# Power_Board.net
KiCad netlist of a schematic drawn in Altium Designer
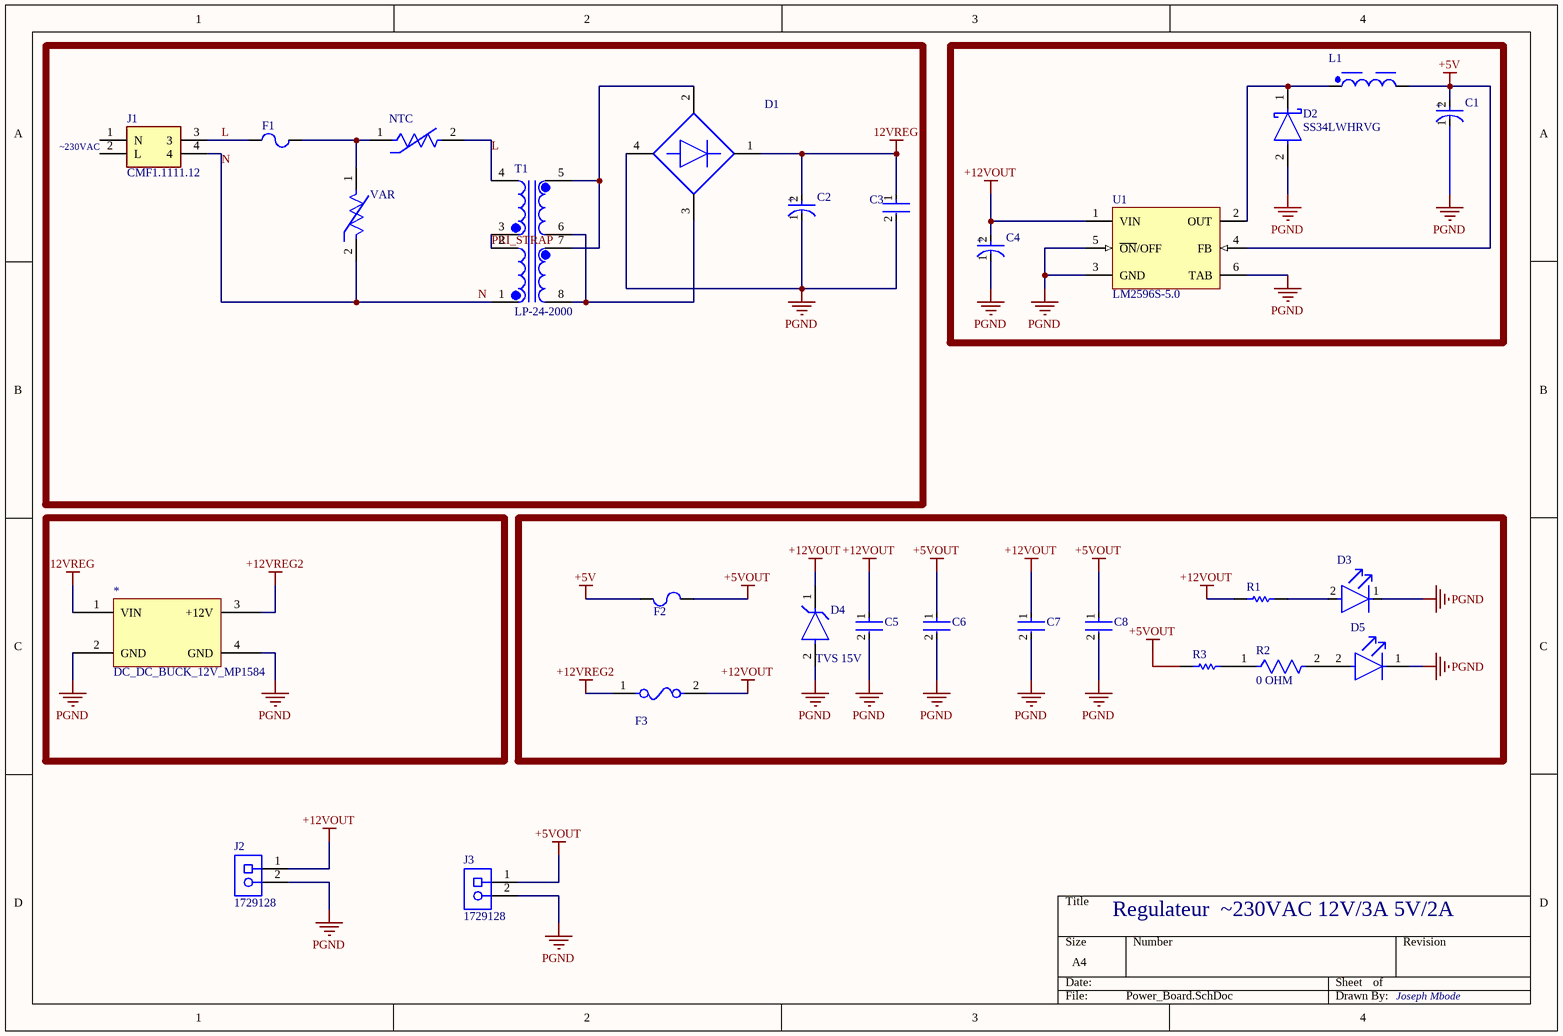
[diagram p0: Power_Board.SchDoc]

(export (version "E")
  (design (tool "Eeschema 10.0.6"))
  (components
    (comp (ref "*")
      (value "DC_DC_BUCK_12V_MP1584")
      (footprint "DC_DC_BUCK_12V_MP1584")
      (libsource (lib "Power_Modules") (part "DC_DC_BUCK_12V_MP1584"))
    )
    (comp (ref "C1")
      (value "EEVTG1H221Q")
      (footprint "FP-TGH13-MFG")
      (description "CAP ALUM 220UF 20% 50V SMD")
      (fields
        (field (name "MANUFACTURER") "Panasonic Electronic Components")
        (field (name "TOLERANCE") "20%")
      )
      (libsource (lib "Altium Content Vault") (part "cf48714ba7e38822c1575c7ec0b6d1f"))
    )
    (comp (ref "C2")
      (value "ECA1VHG472")
      (footprint "FP-RAD-TH-D_18_0_5-L_35_5-MFG")
      (description "Aluminum Electrolytic Capacitors (Radial Lead Type) AEC-Q200 Qualified 4700uF ±20% 35V")
      (fields (field (name "VOLTAGE") "35V") (field (name "TOLERANCE") "20%"))
      (libsource (lib "Altium Content Vault") (part "203bc49f2ac43e59fd269a8c329ed05"))
    )
    (comp (ref "C3")
      (value "RHEL81H155K2A2H03B")
      (footprint "FP-RHE2DB-MFG")
      (description "Ceramic Capacitor Automotive 1.5uF ±10% 50V X8L Radial")
      (fields (field (name "TOLERANCE") "10%"))
      (libsource (lib "Altium Content Vault") (part "02cd4be3c70576c341d710602a673aa"))
    )
    (comp (ref "C4")
      (value "EEUFR1E221")
      (footprint "FP-RAD-TH-D_8_0_5-L_11_5-MFG")
      (description "Aluminum Electrolytic Capacitors (Radial Lead Type) 220uF ±20% 25V")
      (fields (field (name "VOLTAGE") "25V") (field (name "TOLERANCE") "20%"))
      (libsource (lib "Altium Content Vault") (part "a00bbbee19879c290e62620ae7e47b1"))
    )
    (comp (ref "C5")
      (value "AC1206KKX7R0BB104")
      (footprint "FP-AC1206-0_85-MFG")
      (description "CAP CER 0.1UF 100V X7R 1206")
      (fields
        (field (name "OCTOPART") "https://octopart.com/ac1206kkx7r0bb104-yageo-75666120")
        (field (name "TOLERANCE") "0.1")
      )
      (libsource (lib "Altium Content Vault") (part "11868f565c42a9108669ba33697ecf6"))
    )
    (comp (ref "C6")
      (value "AC1206KKX7R0BB104")
      (footprint "FP-AC1206-0_85-MFG")
      (description "CAP CER 0.1UF 100V X7R 1206")
      (fields
        (field (name "OCTOPART") "https://octopart.com/ac1206kkx7r0bb104-yageo-75666120")
        (field (name "TOLERANCE") "0.1")
      )
      (libsource (lib "Altium Content Vault") (part "11868f565c42a9108669ba33697ecf6"))
    )
    (comp (ref "C7")
      (value "AC1206KKX7R0BB104")
      (footprint "FP-AC1206-0_85-MFG")
      (description "CAP CER 0.1UF 100V X7R 1206")
      (fields
        (field (name "OCTOPART") "https://octopart.com/ac1206kkx7r0bb104-yageo-75666120")
        (field (name "TOLERANCE") "0.1")
      )
      (libsource (lib "Altium Content Vault") (part "11868f565c42a9108669ba33697ecf6"))
    )
    (comp (ref "C8")
      (value "AC1206KKX7R0BB104")
      (footprint "FP-AC1206-0_85-MFG")
      (description "CAP CER 0.1UF 100V X7R 1206")
      (fields
        (field (name "OCTOPART") "https://octopart.com/ac1206kkx7r0bb104-yageo-75666120")
        (field (name "TOLERANCE") "0.1")
      )
      (libsource (lib "Altium Content Vault") (part "11868f565c42a9108669ba33697ecf6"))
    )
    (comp (ref "D1")
      (value "GBU4M-E3/51")
      (footprint "FP-GBU4M-E3-51-MFG")
      (description "BRIDGE RECT 1PHASE 1KV 3A GBU")
      (libsource (lib "Altium Content Vault") (part "df980e46bdef61da3a5be2ae2fed6b6"))
    )
    (comp (ref "D2")
      (value "SS34LWHRVG")
      (footprint "FP-SS34LWH-MFG")
      (description "DIODE SCHOTTKY 40V 3A SOD123W")
      (libsource (lib "Altium Content Vault") (part "1d6ec82d83fb6aee721767c19dac4b9"))
    )
    (comp (ref "D3")
      (value "XLUR12D")
      (footprint "FP-XLUR12D-MFG")
      (description "627nm Red LED; 5x8.6mm, Through-Hole Mount with Red Diffused Round Lamp")
      (libsource (lib "Altium Content Vault") (part "XLUR12D"))
    )
    (comp (ref "D4")
      (value "TVS 15V")
      (footprint "FP-DO-15-MFG")
      (description "P6KE15A 600 Watt SUR40 Transient Voltage Suppressor, 15 V, Unidirectional")
      (libsource (lib "Altium Content Vault") (part "f813f71cba58e380607f5dd3caf9714"))
    )
    (comp (ref "D5")
      (value "SSL-LX5093YD")
      (footprint "FP-SSL-LX5093YD-MFG")
      (description "LED YELLOW DIFFUSED T-1 3/4 T/H")
      (libsource (lib "Altium Content Vault") (part "8706943c75ba83719d021d2fdc84c58"))
    )
    (comp (ref "F1")
      (value "021502.5MXP")
      (footprint "LFUS-0215-20X5_L")
      (description "Time-Lag Type Cartridge Fuse, 2.5 A, 0.00386 Ohm, 250 V, -55 to 125 degC, 2-Pin SMD, RoHS, Bulk")
      (fields (field (name "MANUFACTURER") "Littelfuse"))
      (libsource (lib "Altium Content Vault") (part "FUSE-2"))
    )
    (comp (ref "F2")
      (value "1812L150ZR")
      (footprint "LFUS-FUSE1812-71_V")
      (description "Resettable PTC, 1812, 1.5 A Ihold, 3.0 A Itrip")
      (libsource (lib "Altium Content Vault") (part "LFUS-FUSE-2"))
    )
    (comp (ref "F3")
      (value "0452004.MRL")
      (footprint "FP-0452-MFG")
      (description "FUSE BRD MNT 4A 125VAC/VDC 2SMD")
      (fields
        (field (name "MANUFACTURER") "Littelfuse Inc")
        (field (name "OCTOPART") "https://octopart.com/0452004.mrl-littelfuse-566421")
      )
      (libsource (lib "Altium Content Vault") (part "5bcf9b9f640e542cf0359d10258e979"))
    )
    (comp (ref "J1")
      (value "CMF1.1111.12")
      (footprint "CMF1111112")
      (fields (field (name "MOUSER PART NUMBER") "693-CMF1.1111.12"))
      (libsource (lib "connecteur CMF1.1111.12") (part "CMF1.1111.12"))
    )
    (comp (ref "J2")
      (value "1729128")
      (footprint "PHOE-1729128-2_V")
      (description "PCB Terminal Block, 13.5 A, 400 V, 2-Pin THD, RoHS, Bulk")
      (fields (field (name "MANUFACTURER") "Phoenix Contact"))
      (libsource (lib "Bornier_tension") (part "CMP-2000-05815-1"))
    )
    (comp (ref "J3")
      (value "1729128")
      (footprint "PHOE-1729128-2_V")
      (description "PCB Terminal Block, 13.5 A, 400 V, 2-Pin THD, RoHS, Bulk")
      (fields (field (name "MANUFACTURER") "Phoenix Contact"))
      (libsource (lib "Bornier_tension") (part "CMP-2000-05815-1"))
    )
    (comp (ref "L1")
      (value "7447471330")
      (footprint "WE-TIS_1111")
      (description "Inductor Power Shielded Wirewound 33uH 20% 1KHz Ferrite 3.6A 61mOhm DCR RDL Tray")
      (fields (field (name "TOLERANCE") "20%"))
      (libsource (lib "Altium Content Vault") (part "Inductor - 2"))
    )
    (comp (ref "NTC")
      (value "NTPAA100LDNB0")
      (footprint "FP-NTPAA-MFG")
      (description "ICL 10 OHM 15% 1.7A 10MM")
      (fields (field (name "TOLERANCE") "15%"))
      (libsource (lib "Altium Content Vault") (part "3b148a6ebabc5fb4d708a66c052d352"))
    )
    (comp (ref "R1")
      (value "3R3 5% 0805(2012)")
      (footprint "RESC0805(2012)_M")
      (description "3R3 0.125W 5% 0805 (2012 Metric)  SMD")
      (fields (field (name "TOLERANCE") "5 %") (field (name "POWER") "0.125 W"))
      (libsource (lib "Altium Content Vault") (part "RES"))
    )
    (comp (ref "R2")
      (value "0 OHM")
      (footprint "FP-CRG0402-IPC_C")
      (description "RES SMD 0 OHM JUMPER 1/16W 0402")
      (fields (field (name "TOLERANCE") "0%"))
      (libsource (lib "Altium Content Vault") (part "1029c3af85768c4190bb7ad29bc67b5"))
    )
    (comp (ref "R3")
      (value "3R3 5% 0805(2012)")
      (footprint "RESC0805(2012)_M")
      (description "3R3 0.125W 5% 0805 (2012 Metric)  SMD")
      (fields (field (name "TOLERANCE") "5 %") (field (name "POWER") "0.125 W"))
      (libsource (lib "Altium Content Vault") (part "RES"))
    )
    (comp (ref "T1")
      (value "LP-24-2000")
      (footprint "XFMR_LP-24-2000")
      (fields (field (name "MF") "Signal Transformer"))
      (libsource (lib "LP-24-2000") (part "LP-24-2000"))
    )
    (comp (ref "U1")
      (value "LM2596S-5.0")
      (footprint "KTT0005B_L")
      (description "SIMPLE SWITCHER® Power Converter 150 KHz 3A Step-Down Voltage Regulator, 5-pin TO-263")
      (fields (field (name "MANUFACTURER") "Texas Instruments"))
      (libsource (lib "Altium Content Vault") (part "PM-REG-LM2575HVS-12"))
    )
    (comp (ref "VAR")
      (value "IsoM5-275-B-L2")
      (footprint "FP-IsoM5-275-B-L2-MFG")
      (description "ISOMOV 5KA 275VRMS BULK IN-LINE")
      (libsource (lib "Altium Content Vault") (part "661cf0b00536afddc445d021c1166cc"))
    )
  )
  (nets
    (net (code "1") (name "+5V") (class "Default")
      (node (ref "C1") (pin "2") (pinfunction "A_2") (pintype "passive"))
      (node (ref "F2") (pin "1") (pinfunction "1_1") (pintype "passive"))
      (node (ref "L1") (pin "2") (pinfunction "2_2") (pintype "passive"))
      (node (ref "U1") (pin "4") (pinfunction "FB_4") (pintype "input"))
    )
    (net (code "2") (name "+5VOUT") (class "Default")
      (node (ref "C6") (pin "1") (pinfunction "1_1") (pintype "passive"))
      (node (ref "C8") (pin "1") (pinfunction "1_1") (pintype "passive"))
      (node (ref "F2") (pin "2") (pinfunction "2_2") (pintype "passive"))
      (node (ref "J3") (pin "1") (pinfunction "1_1") (pintype "passive"))
      (node (ref "R3") (pin "1") (pinfunction "1_1") (pintype "passive"))
    )
    (net (code "3") (name "+12VOUT") (class "Default")
      (node (ref "C4") (pin "2") (pinfunction "A_2") (pintype "passive"))
      (node (ref "C5") (pin "1") (pinfunction "1_1") (pintype "passive"))
      (node (ref "C7") (pin "1") (pinfunction "1_1") (pintype "passive"))
      (node (ref "D4") (pin "1") (pinfunction "C_1") (pintype "passive"))
      (node (ref "F3") (pin "2") (pinfunction "2_2") (pintype "passive"))
      (node (ref "J2") (pin "1") (pinfunction "1_1") (pintype "passive"))
      (node (ref "R1") (pin "1") (pinfunction "1_1") (pintype "passive"))
      (node (ref "U1") (pin "1") (pinfunction "VIN_1") (pintype "power_in"))
    )
    (net (code "4") (name "+12VREG2") (class "Default")
      (node (ref "*") (pin "3") (pinfunction "+12V_3") (pintype "passive"))
      (node (ref "F3") (pin "1") (pinfunction "1_1") (pintype "passive"))
    )
    (net (code "5") (name "/L") (class "Default")
      (node (ref "F1") (pin "1") (pinfunction "1_1") (pintype "passive"))
      (node (ref "J1") (pin "3") (pinfunction "3_3") (pintype "passive"))
      (node (ref "NTC") (pin "2") (pinfunction "2_2") (pintype "passive"))
      (node (ref "T1") (pin "4") (pinfunction "4_4") (pintype "passive"))
    )
    (net (code "6") (name "/N") (class "Default")
      (node (ref "J1") (pin "4") (pinfunction "4_4") (pintype "passive"))
      (node (ref "T1") (pin "1") (pinfunction "1_1") (pintype "passive"))
      (node (ref "VAR") (pin "2") (pinfunction "2_2") (pintype "passive"))
    )
    (net (code "7") (name "/PRI_STRAP") (class "Default")
      (node (ref "T1") (pin "2") (pinfunction "2_2") (pintype "passive"))
      (node (ref "T1") (pin "3") (pinfunction "3_3") (pintype "passive"))
    )
    (net (code "8") (name "12VREG") (class "Default")
      (node (ref "*") (pin "1") (pinfunction "VIN_1") (pintype "passive"))
      (node (ref "C2") (pin "2") (pinfunction "A_2") (pintype "passive"))
      (node (ref "C3") (pin "1") (pinfunction "1_1") (pintype "passive"))
      (node (ref "D1") (pin "1") (pinfunction "+_1") (pintype "passive"))
    )
    (net (code "9") (name "Net-(D1-1_~)") (class "Default")
      (node (ref "D1") (pin "2") (pinfunction "1_~_2") (pintype "passive"))
      (node (ref "T1") (pin "5") (pinfunction "5_5") (pintype "passive"))
      (node (ref "T1") (pin "7") (pinfunction "7_7") (pintype "passive"))
    )
    (net (code "10") (name "Net-(D1-2_~)") (class "Default")
      (node (ref "D1") (pin "3") (pinfunction "2_~_3") (pintype "passive"))
      (node (ref "T1") (pin "6") (pinfunction "6_6") (pintype "passive"))
      (node (ref "T1") (pin "8") (pinfunction "8_8") (pintype "passive"))
    )
    (net (code "11") (name "Net-(D2-C)") (class "Default")
      (node (ref "D2") (pin "1") (pinfunction "C_1") (pintype "passive"))
      (node (ref "L1") (pin "1") (pinfunction "1_1") (pintype "passive"))
      (node (ref "U1") (pin "2") (pinfunction "OUT_2") (pintype "power_in"))
    )
    (net (code "12") (name "Net-(D3-A)") (class "Default")
      (node (ref "D3") (pin "2") (pinfunction "A_2") (pintype "passive"))
      (node (ref "R1") (pin "2") (pinfunction "2_2") (pintype "passive"))
    )
    (net (code "13") (name "Net-(D5-A)") (class "Default")
      (node (ref "D5") (pin "2") (pinfunction "A_2") (pintype "passive"))
      (node (ref "R2") (pin "2") (pinfunction "2_2") (pintype "passive"))
    )
    (net (code "14") (name "Net-(F1-Pad2)") (class "Default")
      (node (ref "F1") (pin "2") (pinfunction "2_2") (pintype "passive"))
      (node (ref "NTC") (pin "1") (pinfunction "1_1") (pintype "passive"))
      (node (ref "VAR") (pin "1") (pinfunction "1_1") (pintype "passive"))
    )
    (net (code "15") (name "Net-(R2-Pad1)") (class "Default")
      (node (ref "R2") (pin "1") (pinfunction "1_1") (pintype "passive"))
      (node (ref "R3") (pin "2") (pinfunction "2_2") (pintype "passive"))
    )
    (net (code "16") (name "PGND") (class "Default")
      (node (ref "*") (pin "2") (pinfunction "GND_2") (pintype "passive"))
      (node (ref "*") (pin "4") (pinfunction "GND_4") (pintype "passive"))
      (node (ref "C1") (pin "1") (pinfunction "C_1") (pintype "passive"))
      (node (ref "C2") (pin "1") (pinfunction "C_1") (pintype "passive"))
      (node (ref "C3") (pin "2") (pinfunction "2_2") (pintype "passive"))
      (node (ref "C4") (pin "1") (pinfunction "C_1") (pintype "passive"))
      (node (ref "C5") (pin "2") (pinfunction "2_2") (pintype "passive"))
      (node (ref "C6") (pin "2") (pinfunction "2_2") (pintype "passive"))
      (node (ref "C7") (pin "2") (pinfunction "2_2") (pintype "passive"))
      (node (ref "C8") (pin "2") (pinfunction "2_2") (pintype "passive"))
      (node (ref "D1") (pin "4") (pinfunction "-_4") (pintype "passive"))
      (node (ref "D2") (pin "2") (pinfunction "A_2") (pintype "passive"))
      (node (ref "D3") (pin "1") (pinfunction "C_1") (pintype "passive"))
      (node (ref "D4") (pin "2") (pinfunction "A_2") (pintype "passive"))
      (node (ref "D5") (pin "1") (pinfunction "C_1") (pintype "passive"))
      (node (ref "J2") (pin "2") (pinfunction "2_2") (pintype "passive"))
      (node (ref "J3") (pin "2") (pinfunction "2_2") (pintype "passive"))
      (node (ref "U1") (pin "3") (pinfunction "GND_3") (pintype "power_in"))
      (node (ref "U1") (pin "5") (pinfunction "~{ON}/OFF_5") (pintype "input"))
      (node (ref "U1") (pin "6") (pinfunction "TAB_6") (pintype "power_in"))
    )
    (net (code "17") (name "unconnected-(J1-L-Pad2)") (class "Default")
      (node (ref "J1") (pin "2") (pinfunction "L_2") (pintype "passive"))
    )
    (net (code "18") (name "unconnected-(J1-N-Pad1)") (class "Default")
      (node (ref "J1") (pin "1") (pinfunction "N_1") (pintype "passive"))
    )
  )
)
